# MKX-controller.net
KiCad netlist of a schematic drawn in EAGLE
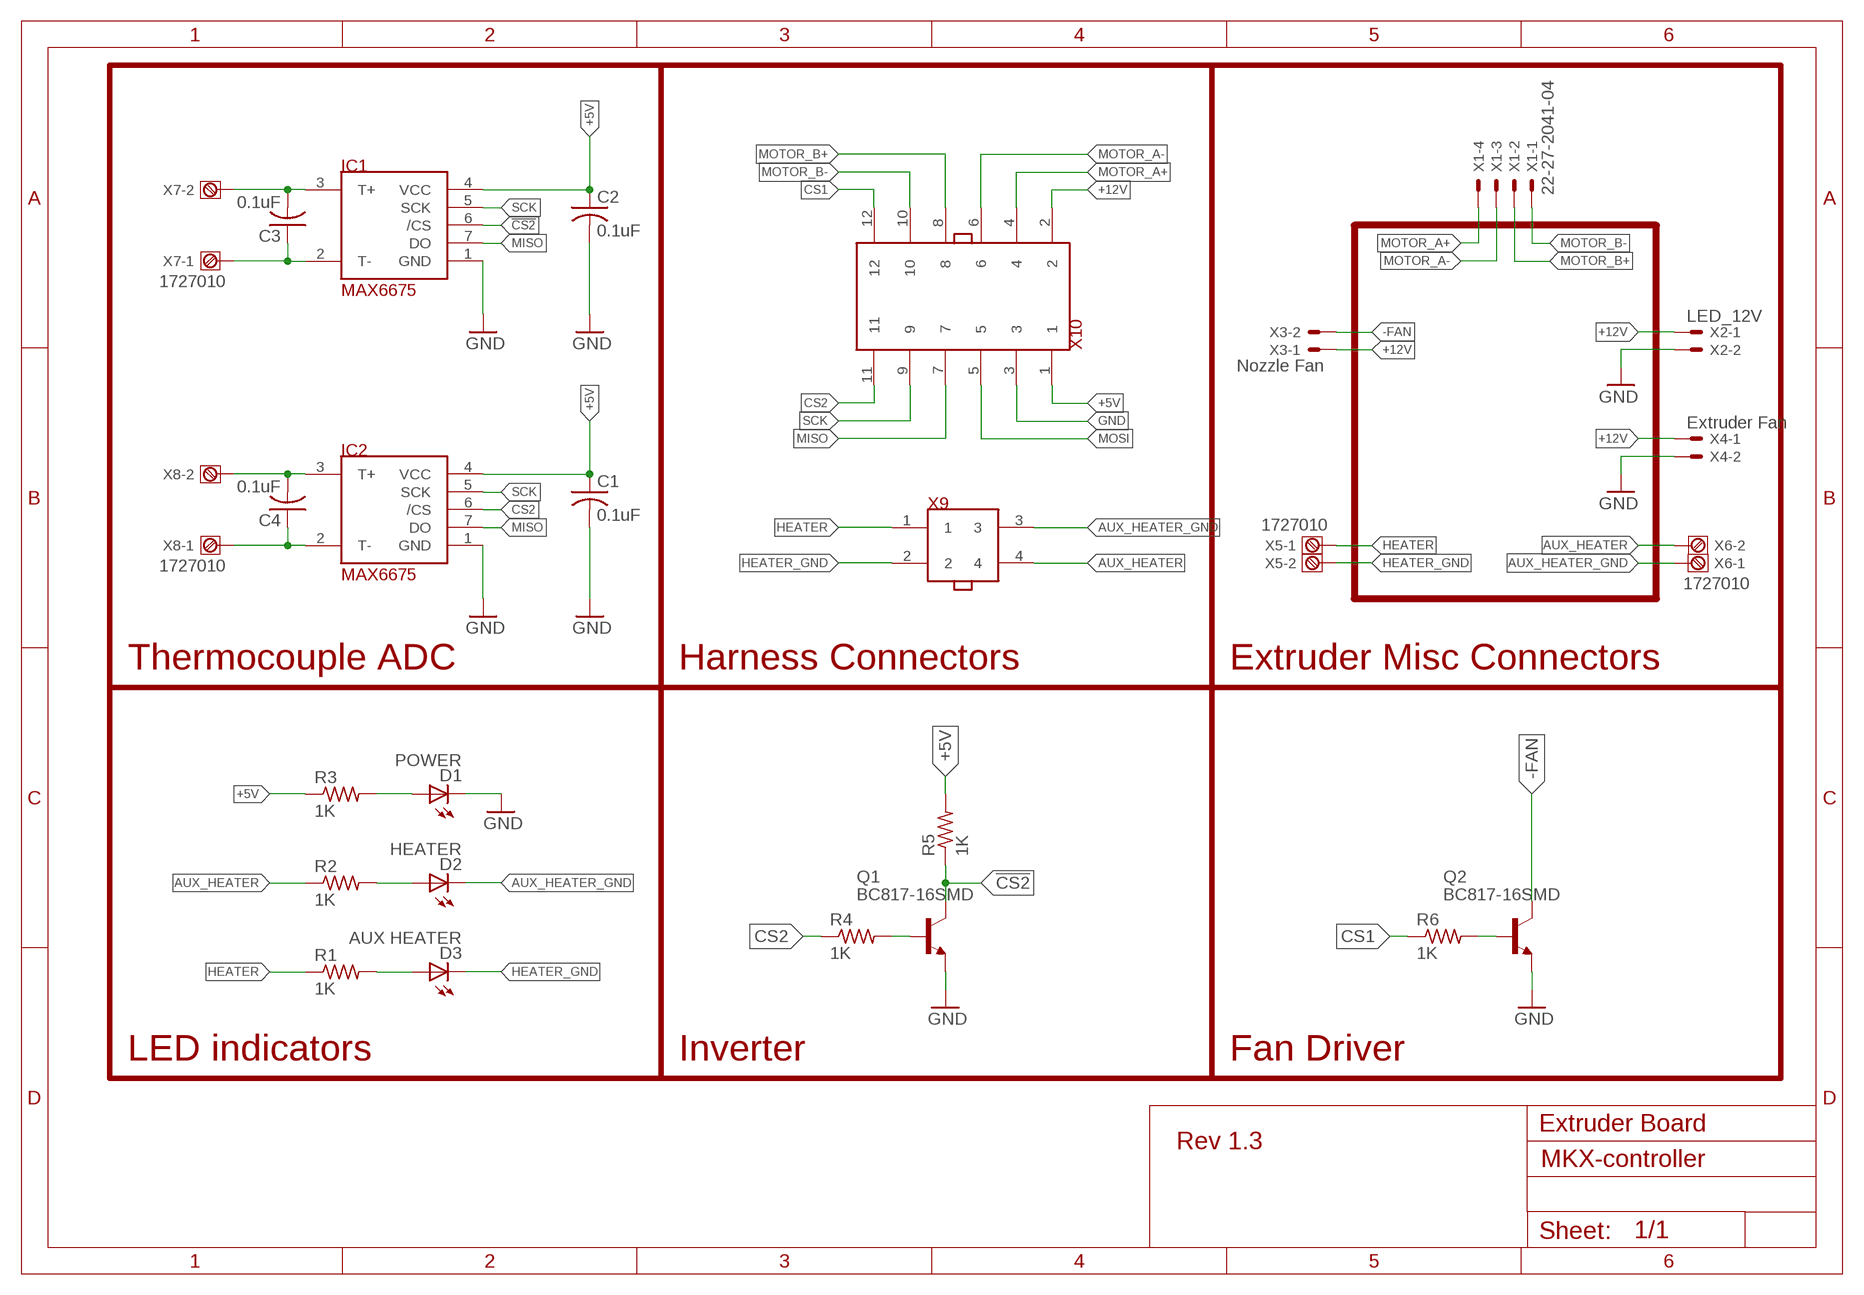
[diagram p0: schematic, sheet 1]

(export (version "E")
  (design (tool "Eeschema 10.0.6"))
  (components
    (comp (ref "C1")
      (value "0.1uF")
      (footprint "eagle-import:C0603K")
      (libsource (lib "eagle-import") (part "C-USC0603K"))
    )
    (comp (ref "C2")
      (value "0.1uF")
      (footprint "eagle-import:C0603K")
      (libsource (lib "eagle-import") (part "C-USC0603K"))
    )
    (comp (ref "C3")
      (value "0.1uF")
      (footprint "eagle-import:C0603K")
      (libsource (lib "eagle-import") (part "C-USC0603K"))
    )
    (comp (ref "C4")
      (value "0.1uF")
      (footprint "eagle-import:C0603K")
      (libsource (lib "eagle-import") (part "C-USC0603K"))
    )
    (comp (ref "D1")
      (value "POWER")
      (footprint "eagle-import:CHIPLED_0805")
      (libsource (lib "eagle-import") (part "LEDCHIPLED_0805"))
    )
    (comp (ref "D2")
      (value "HEATER")
      (footprint "eagle-import:CHIPLED_0805")
      (libsource (lib "eagle-import") (part "LEDCHIPLED_0805"))
    )
    (comp (ref "D3")
      (value "AUX HEATER")
      (footprint "eagle-import:CHIPLED_0805")
      (libsource (lib "eagle-import") (part "LEDCHIPLED_0805"))
    )
    (comp (ref "IC1")
      (value "MAX6675")
      (footprint "eagle-import:SO-8")
      (libsource (lib "eagle-import") (part "MAX6675"))
    )
    (comp (ref "IC2")
      (value "MAX6675")
      (footprint "eagle-import:SO-8")
      (libsource (lib "eagle-import") (part "MAX6675"))
    )
    (comp (ref "Q1")
      (value "BC817-16SMD")
      (footprint "eagle-import:SOT23-BEC")
      (libsource (lib "eagle-import") (part "BC817SMD-16"))
    )
    (comp (ref "Q2")
      (value "BC817-16SMD")
      (footprint "eagle-import:SOT23-BEC")
      (libsource (lib "eagle-import") (part "BC817SMD-16"))
    )
    (comp (ref "R1")
      (value "1K")
      (footprint "eagle-import:R0603")
      (libsource (lib "eagle-import") (part "R-US_R0603"))
    )
    (comp (ref "R2")
      (value "1K")
      (footprint "eagle-import:R0603")
      (libsource (lib "eagle-import") (part "R-US_R0603"))
    )
    (comp (ref "R3")
      (value "1K")
      (footprint "eagle-import:R0603")
      (libsource (lib "eagle-import") (part "R-US_R0603"))
    )
    (comp (ref "R4")
      (value "1K")
      (footprint "eagle-import:R0603")
      (libsource (lib "eagle-import") (part "R-US_R0603"))
    )
    (comp (ref "R5")
      (value "1K")
      (footprint "eagle-import:R0603")
      (libsource (lib "eagle-import") (part "R-US_R0603"))
    )
    (comp (ref "R6")
      (value "1K")
      (footprint "eagle-import:R0603")
      (libsource (lib "eagle-import") (part "R-US_R0603"))
    )
    (comp (ref "X1")
      (value "22-27-2041-04")
      (footprint "eagle-import:6410-04")
      (fields (field (name "OC_FARNELL") "unknown") (field (name "OC_NEWARK") "unknown"))
      (libsource (lib "eagle-import") (part "22-?-0427-2041"))
    )
    (comp (ref "X2")
      (value "LED_12V")
      (footprint "eagle-import:6410-02")
      (fields (field (name "OC_FARNELL") "unknown") (field (name "OC_NEWARK") "unknown"))
      (libsource (lib "eagle-import") (part "22-?-0227-2021"))
    )
    (comp (ref "X3")
      (value "Nozzle Fan")
      (footprint "eagle-import:6410-02")
      (fields (field (name "OC_FARNELL") "unknown") (field (name "OC_NEWARK") "unknown"))
      (libsource (lib "eagle-import") (part "22-?-0227-2021"))
    )
    (comp (ref "X4")
      (value "Extruder Fan")
      (footprint "eagle-import:6410-02")
      (fields (field (name "OC_FARNELL") "unknown") (field (name "OC_NEWARK") "unknown"))
      (libsource (lib "eagle-import") (part "22-?-0227-2021"))
    )
    (comp (ref "X5")
      (value "1727010")
      (footprint "eagle-import:1727010")
      (libsource (lib "eagle-import") (part "1727010"))
    )
    (comp (ref "X6")
      (value "1727010")
      (footprint "eagle-import:1727010")
      (libsource (lib "eagle-import") (part "1727010"))
    )
    (comp (ref "X7")
      (value "1727010")
      (footprint "eagle-import:1727010")
      (libsource (lib "eagle-import") (part "1727010"))
    )
    (comp (ref "X8")
      (value "1727010")
      (footprint "eagle-import:1727010")
      (libsource (lib "eagle-import") (part "1727010"))
    )
    (comp (ref "X9")
      (value "5557-04")
      (footprint "eagle-import:5557-04")
      (libsource (lib "eagle-import") (part "5557-04"))
    )
    (comp (ref "X10")
      (value "5557-12")
      (footprint "eagle-import:5557-12")
      (libsource (lib "eagle-import") (part "5557-12"))
    )
  )
  (nets
    (net (code "1") (name "+5V") (class "Default")
      (node (ref "C1") (pin "1") (pinfunction "1_1") (pintype "passive"))
      (node (ref "C2") (pin "1") (pinfunction "1_1") (pintype "passive"))
      (node (ref "IC1") (pin "4") (pinfunction "VCC_4") (pintype "bidirectional"))
      (node (ref "IC2") (pin "4") (pinfunction "VCC_4") (pintype "bidirectional"))
      (node (ref "R3") (pin "1") (pinfunction "1_1") (pintype "passive"))
      (node (ref "R5") (pin "2") (pinfunction "2_2") (pintype "passive"))
      (node (ref "X10") (pin "1") (pinfunction "1_1") (pintype "bidirectional"))
    )
    (net (code "2") (name "+12V") (class "Default")
      (node (ref "X10") (pin "2") (pinfunction "2_2") (pintype "bidirectional"))
      (node (ref "X2") (pin "1") (pinfunction "S_1") (pintype "passive"))
      (node (ref "X3") (pin "1") (pinfunction "S_1") (pintype "passive"))
      (node (ref "X4") (pin "1") (pinfunction "S_1") (pintype "passive"))
    )
    (net (code "3") (name "-FAN") (class "Default")
      (node (ref "Q2") (pin "C") (pinfunction "C_C") (pintype "passive"))
      (node (ref "X3") (pin "2") (pinfunction "S_2") (pintype "passive"))
    )
    (net (code "4") (name "/~{CS2}") (class "Default")
      (node (ref "IC1") (pin "6") (pinfunction "/CS_6") (pintype "bidirectional"))
      (node (ref "Q1") (pin "C") (pinfunction "C_C") (pintype "passive"))
      (node (ref "R5") (pin "1") (pinfunction "1_1") (pintype "passive"))
    )
    (net (code "5") (name "AUX_HEATER") (class "Default")
      (node (ref "R2") (pin "1") (pinfunction "1_1") (pintype "passive"))
      (node (ref "X6") (pin "2") (pinfunction "1_2") (pintype "passive"))
      (node (ref "X9") (pin "4") (pinfunction "4_4") (pintype "bidirectional"))
    )
    (net (code "6") (name "AUX_HEATER_GND") (class "Default")
      (node (ref "D2") (pin "C") (pinfunction "C_C") (pintype "passive"))
      (node (ref "X6") (pin "1") (pinfunction "1_1") (pintype "passive"))
      (node (ref "X9") (pin "3") (pinfunction "3_3") (pintype "bidirectional"))
    )
    (net (code "7") (name "CS1") (class "Default")
      (node (ref "R6") (pin "1") (pinfunction "1_1") (pintype "passive"))
      (node (ref "X10") (pin "12") (pinfunction "12_12") (pintype "bidirectional"))
    )
    (net (code "8") (name "CS2") (class "Default")
      (node (ref "IC2") (pin "6") (pinfunction "/CS_6") (pintype "bidirectional"))
      (node (ref "R4") (pin "1") (pinfunction "1_1") (pintype "passive"))
      (node (ref "X10") (pin "11") (pinfunction "11_11") (pintype "bidirectional"))
    )
    (net (code "9") (name "GND") (class "Default")
      (node (ref "C1") (pin "2") (pinfunction "2_2") (pintype "passive"))
      (node (ref "C2") (pin "2") (pinfunction "2_2") (pintype "passive"))
      (node (ref "D1") (pin "C") (pinfunction "C_C") (pintype "passive"))
      (node (ref "IC1") (pin "1") (pinfunction "GND_1") (pintype "bidirectional"))
      (node (ref "IC2") (pin "1") (pinfunction "GND_1") (pintype "bidirectional"))
      (node (ref "Q1") (pin "E") (pinfunction "E_E") (pintype "passive"))
      (node (ref "Q2") (pin "E") (pinfunction "E_E") (pintype "passive"))
      (node (ref "X10") (pin "3") (pinfunction "3_3") (pintype "bidirectional"))
      (node (ref "X2") (pin "2") (pinfunction "S_2") (pintype "passive"))
      (node (ref "X4") (pin "2") (pinfunction "S_2") (pintype "passive"))
    )
    (net (code "10") (name "HEATER") (class "Default")
      (node (ref "R1") (pin "1") (pinfunction "1_1") (pintype "passive"))
      (node (ref "X5") (pin "1") (pinfunction "1_1") (pintype "passive"))
      (node (ref "X9") (pin "1") (pinfunction "1_1") (pintype "bidirectional"))
    )
    (net (code "11") (name "HEATER_GND") (class "Default")
      (node (ref "D3") (pin "C") (pinfunction "C_C") (pintype "passive"))
      (node (ref "X5") (pin "2") (pinfunction "1_2") (pintype "passive"))
      (node (ref "X9") (pin "2") (pinfunction "2_2") (pintype "bidirectional"))
    )
    (net (code "12") (name "MISO") (class "Default")
      (node (ref "IC1") (pin "7") (pinfunction "DO_7") (pintype "bidirectional"))
      (node (ref "IC2") (pin "7") (pinfunction "DO_7") (pintype "bidirectional"))
      (node (ref "X10") (pin "7") (pinfunction "7_7") (pintype "bidirectional"))
    )
    (net (code "13") (name "MOSI") (class "Default")
      (node (ref "X10") (pin "5") (pinfunction "5_5") (pintype "bidirectional"))
    )
    (net (code "14") (name "MOTOR_A+") (class "Default")
      (node (ref "X1") (pin "4") (pinfunction "S_4") (pintype "passive"))
      (node (ref "X10") (pin "4") (pinfunction "4_4") (pintype "bidirectional"))
    )
    (net (code "15") (name "MOTOR_A-") (class "Default")
      (node (ref "X1") (pin "3") (pinfunction "S_3") (pintype "passive"))
      (node (ref "X10") (pin "6") (pinfunction "6_6") (pintype "bidirectional"))
    )
    (net (code "16") (name "MOTOR_B+") (class "Default")
      (node (ref "X1") (pin "2") (pinfunction "S_2") (pintype "passive"))
      (node (ref "X10") (pin "8") (pinfunction "8_8") (pintype "bidirectional"))
    )
    (net (code "17") (name "MOTOR_B-") (class "Default")
      (node (ref "X1") (pin "1") (pinfunction "S_1") (pintype "passive"))
      (node (ref "X10") (pin "10") (pinfunction "10_10") (pintype "bidirectional"))
    )
    (net (code "18") (name "Net-(D1-PadA)") (class "Default")
      (node (ref "D1") (pin "A") (pinfunction "A_A") (pintype "passive"))
      (node (ref "R3") (pin "2") (pinfunction "2_2") (pintype "passive"))
    )
    (net (code "19") (name "Net-(D2-PadA)") (class "Default")
      (node (ref "D2") (pin "A") (pinfunction "A_A") (pintype "passive"))
      (node (ref "R2") (pin "2") (pinfunction "2_2") (pintype "passive"))
    )
    (net (code "20") (name "Net-(D3-PadA)") (class "Default")
      (node (ref "D3") (pin "A") (pinfunction "A_A") (pintype "passive"))
      (node (ref "R1") (pin "2") (pinfunction "2_2") (pintype "passive"))
    )
    (net (code "21") (name "Net-(IC1-T+)") (class "Default")
      (node (ref "C3") (pin "2") (pinfunction "2_2") (pintype "passive"))
      (node (ref "IC1") (pin "3") (pinfunction "T+_3") (pintype "bidirectional"))
      (node (ref "X7") (pin "2") (pinfunction "1_2") (pintype "passive"))
    )
    (net (code "22") (name "Net-(IC1-T-)") (class "Default")
      (node (ref "C3") (pin "1") (pinfunction "1_1") (pintype "passive"))
      (node (ref "IC1") (pin "2") (pinfunction "T-_2") (pintype "bidirectional"))
      (node (ref "X7") (pin "1") (pinfunction "1_1") (pintype "passive"))
    )
    (net (code "23") (name "Net-(IC2-T+)") (class "Default")
      (node (ref "C4") (pin "2") (pinfunction "2_2") (pintype "passive"))
      (node (ref "IC2") (pin "3") (pinfunction "T+_3") (pintype "bidirectional"))
      (node (ref "X8") (pin "2") (pinfunction "1_2") (pintype "passive"))
    )
    (net (code "24") (name "Net-(IC2-T-)") (class "Default")
      (node (ref "C4") (pin "1") (pinfunction "1_1") (pintype "passive"))
      (node (ref "IC2") (pin "2") (pinfunction "T-_2") (pintype "bidirectional"))
      (node (ref "X8") (pin "1") (pinfunction "1_1") (pintype "passive"))
    )
    (net (code "25") (name "Net-(Q1-PadB)") (class "Default")
      (node (ref "Q1") (pin "B") (pinfunction "B_B") (pintype "passive"))
      (node (ref "R4") (pin "2") (pinfunction "2_2") (pintype "passive"))
    )
    (net (code "26") (name "Net-(Q2-PadB)") (class "Default")
      (node (ref "Q2") (pin "B") (pinfunction "B_B") (pintype "passive"))
      (node (ref "R6") (pin "2") (pinfunction "2_2") (pintype "passive"))
    )
    (net (code "27") (name "SCK") (class "Default")
      (node (ref "IC1") (pin "5") (pinfunction "SCK_5") (pintype "bidirectional"))
      (node (ref "IC2") (pin "5") (pinfunction "SCK_5") (pintype "bidirectional"))
      (node (ref "X10") (pin "9") (pinfunction "9_9") (pintype "bidirectional"))
    )
  )
)
